# Puzzle_Sound_Sensor_v1_0.net
KiCad netlist of a schematic drawn in EAGLE
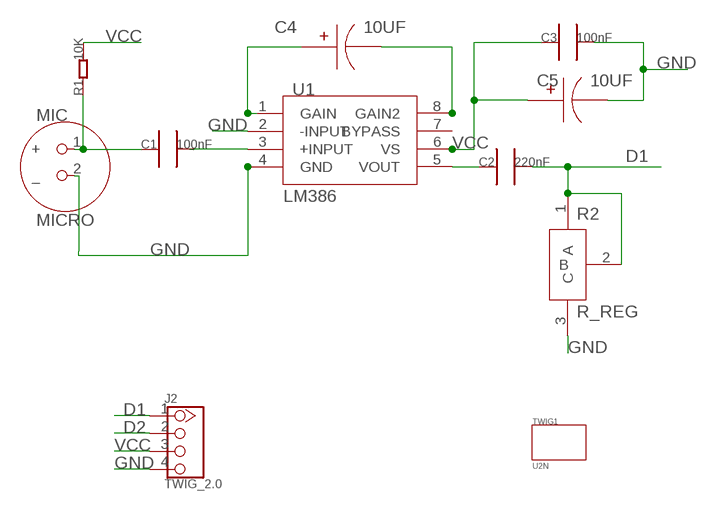
[diagram p0: schematic, sheet 1]

(export (version "E")
  (design (tool "Eeschema 10.0.6"))
  (components
    (comp (ref "C1")
      (value "100nF")
      (footprint "eagle-import:0603")
      (libsource (lib "eagle-import") (part "C0603"))
    )
    (comp (ref "C2")
      (value "220nF")
      (footprint "eagle-import:0603")
      (libsource (lib "eagle-import") (part "C0603"))
    )
    (comp (ref "C3")
      (value "100nF")
      (footprint "eagle-import:0603")
      (libsource (lib "eagle-import") (part "C0603"))
    )
    (comp (ref "C4")
      (value "10UF")
      (footprint "eagle-import:C_TAN1206")
      (libsource (lib "eagle-import") (part "C_TAN1206"))
    )
    (comp (ref "C5")
      (value "10UF")
      (footprint "eagle-import:C_TAN1206")
      (libsource (lib "eagle-import") (part "C_TAN1206"))
    )
    (comp (ref "J2")
      (value "TWIG_2.0")
      (footprint "eagle-import:2.0_1X4")
      (libsource (lib "eagle-import") (part "TWIG_2.0"))
    )
    (comp (ref "MIC")
      (value "MICRO")
      (footprint "eagle-import:MICRO")
      (libsource (lib "eagle-import") (part "MICRO"))
    )
    (comp (ref "R1")
      (value "10K")
      (footprint "eagle-import:0603")
      (libsource (lib "eagle-import") (part "R0603"))
    )
    (comp (ref "R2")
      (value "R_REG")
      (footprint "eagle-import:R_REG")
      (libsource (lib "eagle-import") (part "R_REG"))
    )
    (comp (ref "TWIG1")
      (value "U2N")
      (footprint "eagle-import:U2N")
      (libsource (lib "eagle-import") (part "U2N"))
    )
    (comp (ref "U1")
      (value "LM386")
      (footprint "eagle-import:SO08")
      (libsource (lib "eagle-import") (part "LM386"))
    )
  )
  (nets
    (net (code "1") (name "/D1") (class "Default")
      (node (ref "C2") (pin "2") (pinfunction "2_2") (pintype "bidirectional"))
      (node (ref "J2") (pin "1") (pinfunction "1_1") (pintype "bidirectional"))
      (node (ref "R2") (pin "1") (pinfunction "A_1") (pintype "bidirectional"))
      (node (ref "R2") (pin "2") (pinfunction "B_2") (pintype "bidirectional"))
    )
    (net (code "2") (name "/D2") (class "Default")
      (node (ref "J2") (pin "2") (pinfunction "2_2") (pintype "bidirectional"))
    )
    (net (code "3") (name "/GND") (class "Default")
      (node (ref "C3") (pin "2") (pinfunction "2_2") (pintype "bidirectional"))
      (node (ref "C5") (pin "2") (pinfunction "P$2_2") (pintype "passive"))
      (node (ref "J2") (pin "4") (pinfunction "4_4") (pintype "bidirectional"))
      (node (ref "MIC") (pin "2") (pinfunction "__2") (pintype "bidirectional"))
      (node (ref "R2") (pin "3") (pinfunction "C_3") (pintype "bidirectional"))
      (node (ref "U1") (pin "2") (pinfunction "-INPUT_2") (pintype "bidirectional"))
      (node (ref "U1") (pin "4") (pinfunction "GND_4") (pintype "bidirectional"))
    )
    (net (code "4") (name "/VCC") (class "Default")
      (node (ref "C3") (pin "1") (pinfunction "1_1") (pintype "bidirectional"))
      (node (ref "C5") (pin "1") (pinfunction "P$1_1") (pintype "passive"))
      (node (ref "J2") (pin "3") (pinfunction "3_3") (pintype "bidirectional"))
      (node (ref "R1") (pin "2") (pinfunction "2_2") (pintype "bidirectional"))
      (node (ref "U1") (pin "6") (pinfunction "VS_6") (pintype "bidirectional"))
    )
    (net (code "5") (name "Net-(C4-P$1)") (class "Default")
      (node (ref "C4") (pin "1") (pinfunction "P$1_1") (pintype "passive"))
      (node (ref "U1") (pin "1") (pinfunction "GAIN_1") (pintype "bidirectional"))
    )
    (net (code "6") (name "Net-(C4-P$2)") (class "Default")
      (node (ref "C4") (pin "2") (pinfunction "P$2_2") (pintype "passive"))
      (node (ref "U1") (pin "8") (pinfunction "GAIN2_8") (pintype "bidirectional"))
    )
    (net (code "7") (name "Net-(MIC-+)") (class "Default")
      (node (ref "C1") (pin "1") (pinfunction "1_1") (pintype "bidirectional"))
      (node (ref "MIC") (pin "1") (pinfunction "+_1") (pintype "bidirectional"))
      (node (ref "R1") (pin "1") (pinfunction "1_1") (pintype "bidirectional"))
    )
    (net (code "8") (name "Net-(U1-+INPUT)") (class "Default")
      (node (ref "C1") (pin "2") (pinfunction "2_2") (pintype "bidirectional"))
      (node (ref "U1") (pin "3") (pinfunction "+INPUT_3") (pintype "bidirectional"))
    )
    (net (code "9") (name "Net-(U1-VOUT)") (class "Default")
      (node (ref "C2") (pin "1") (pinfunction "1_1") (pintype "bidirectional"))
      (node (ref "U1") (pin "5") (pinfunction "VOUT_5") (pintype "bidirectional"))
    )
    (net (code "10") (name "unconnected-(U1-BYPASS-Pad7)") (class "Default")
      (node (ref "U1") (pin "7") (pinfunction "BYPASS_7") (pintype "bidirectional"))
    )
  )
)
